# led.net
KiCad netlist of a schematic drawn in EAGLE
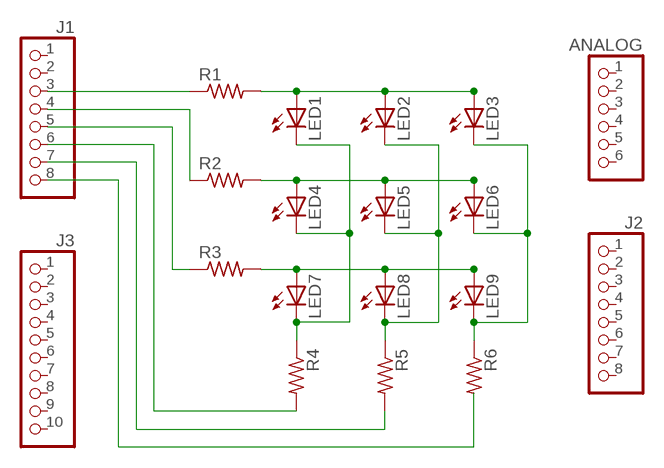
[diagram p0: schematic, sheet 1]

(export (version "E")
  (design (tool "Eeschema 10.0.6"))
  (components
    (comp (ref "ANALOG")
      (value "PINHD-1X6")
      (footprint "eagle-import:1X06")
      (libsource (lib "eagle-import") (part "PINHD-1X6"))
    )
    (comp (ref "J1")
      (value "PINHD-1X8TH")
      (footprint "eagle-import:1X08-TH")
      (libsource (lib "eagle-import") (part "PINHD-1X8TH"))
    )
    (comp (ref "J2")
      (value "PINHD-1X8TH")
      (footprint "eagle-import:1X08-TH")
      (libsource (lib "eagle-import") (part "PINHD-1X8TH"))
    )
    (comp (ref "J3")
      (value "PINHD-1X10TH")
      (footprint "eagle-import:1X10-TH")
      (libsource (lib "eagle-import") (part "PINHD-1X10TH"))
    )
    (comp (ref "LED1")
      (value "LED3MM")
      (footprint "eagle-import:LED3MM")
      (libsource (lib "eagle-import") (part "LED3MM"))
    )
    (comp (ref "LED2")
      (value "LED3MM")
      (footprint "eagle-import:LED3MM")
      (libsource (lib "eagle-import") (part "LED3MM"))
    )
    (comp (ref "LED3")
      (value "LED3MM")
      (footprint "eagle-import:LED3MM")
      (libsource (lib "eagle-import") (part "LED3MM"))
    )
    (comp (ref "LED4")
      (value "LED3MM")
      (footprint "eagle-import:LED3MM")
      (libsource (lib "eagle-import") (part "LED3MM"))
    )
    (comp (ref "LED5")
      (value "LED3MM")
      (footprint "eagle-import:LED3MM")
      (libsource (lib "eagle-import") (part "LED3MM"))
    )
    (comp (ref "LED6")
      (value "LED3MM")
      (footprint "eagle-import:LED3MM")
      (libsource (lib "eagle-import") (part "LED3MM"))
    )
    (comp (ref "LED7")
      (value "LED3MM")
      (footprint "eagle-import:LED3MM")
      (libsource (lib "eagle-import") (part "LED3MM"))
    )
    (comp (ref "LED8")
      (value "LED3MM")
      (footprint "eagle-import:LED3MM")
      (libsource (lib "eagle-import") (part "LED3MM"))
    )
    (comp (ref "LED9")
      (value "LED3MM")
      (footprint "eagle-import:LED3MM")
      (libsource (lib "eagle-import") (part "LED3MM"))
    )
    (comp (ref "R1")
      (value "R-US_0207/10")
      (footprint "eagle-import:0207_10")
      (libsource (lib "eagle-import") (part "R-US_0207/10"))
    )
    (comp (ref "R2")
      (value "R-US_0207/10")
      (footprint "eagle-import:0207_10")
      (libsource (lib "eagle-import") (part "R-US_0207/10"))
    )
    (comp (ref "R3")
      (value "R-US_0207/10")
      (footprint "eagle-import:0207_10")
      (libsource (lib "eagle-import") (part "R-US_0207/10"))
    )
    (comp (ref "R4")
      (value "R-US_0207/10")
      (footprint "eagle-import:0207_10")
      (libsource (lib "eagle-import") (part "R-US_0207/10"))
    )
    (comp (ref "R5")
      (value "R-US_0207/10")
      (footprint "eagle-import:0207_10")
      (libsource (lib "eagle-import") (part "R-US_0207/10"))
    )
    (comp (ref "R6")
      (value "R-US_0207/10")
      (footprint "eagle-import:0207_10")
      (libsource (lib "eagle-import") (part "R-US_0207/10"))
    )
  )
  (nets
    (net (code "1") (name "Net-(J1-Pad3)") (class "Default")
      (node (ref "J1") (pin "3") (pinfunction "3_3") (pintype "passive"))
      (node (ref "R1") (pin "1") (pinfunction "1_1") (pintype "passive"))
    )
    (net (code "2") (name "Net-(J1-Pad4)") (class "Default")
      (node (ref "J1") (pin "4") (pinfunction "4_4") (pintype "passive"))
      (node (ref "R2") (pin "1") (pinfunction "1_1") (pintype "passive"))
    )
    (net (code "3") (name "Net-(J1-Pad5)") (class "Default")
      (node (ref "J1") (pin "5") (pinfunction "5_5") (pintype "passive"))
      (node (ref "R3") (pin "1") (pinfunction "1_1") (pintype "passive"))
    )
    (net (code "4") (name "Net-(J1-Pad6)") (class "Default")
      (node (ref "J1") (pin "6") (pinfunction "6_6") (pintype "passive"))
      (node (ref "R4") (pin "2") (pinfunction "2_2") (pintype "passive"))
    )
    (net (code "5") (name "Net-(J1-Pad7)") (class "Default")
      (node (ref "J1") (pin "7") (pinfunction "7_7") (pintype "passive"))
      (node (ref "R5") (pin "2") (pinfunction "2_2") (pintype "passive"))
    )
    (net (code "6") (name "Net-(J1-Pad8)") (class "Default")
      (node (ref "J1") (pin "8") (pinfunction "8_8") (pintype "passive"))
      (node (ref "R6") (pin "2") (pinfunction "2_2") (pintype "passive"))
    )
    (net (code "7") (name "Net-(LED1-C)") (class "Default")
      (node (ref "LED1") (pin "K") (pinfunction "C_K") (pintype "passive"))
      (node (ref "LED4") (pin "K") (pinfunction "C_K") (pintype "passive"))
      (node (ref "LED7") (pin "K") (pinfunction "C_K") (pintype "passive"))
      (node (ref "R4") (pin "1") (pinfunction "1_1") (pintype "passive"))
    )
    (net (code "8") (name "Net-(LED1-PadA)") (class "Default")
      (node (ref "LED1") (pin "A") (pinfunction "A_A") (pintype "passive"))
      (node (ref "LED2") (pin "A") (pinfunction "A_A") (pintype "passive"))
      (node (ref "LED3") (pin "A") (pinfunction "A_A") (pintype "passive"))
      (node (ref "R1") (pin "2") (pinfunction "2_2") (pintype "passive"))
    )
    (net (code "9") (name "Net-(LED2-C)") (class "Default")
      (node (ref "LED2") (pin "K") (pinfunction "C_K") (pintype "passive"))
      (node (ref "LED5") (pin "K") (pinfunction "C_K") (pintype "passive"))
      (node (ref "LED8") (pin "K") (pinfunction "C_K") (pintype "passive"))
      (node (ref "R5") (pin "1") (pinfunction "1_1") (pintype "passive"))
    )
    (net (code "10") (name "Net-(LED3-C)") (class "Default")
      (node (ref "LED3") (pin "K") (pinfunction "C_K") (pintype "passive"))
      (node (ref "LED6") (pin "K") (pinfunction "C_K") (pintype "passive"))
      (node (ref "LED9") (pin "K") (pinfunction "C_K") (pintype "passive"))
      (node (ref "R6") (pin "1") (pinfunction "1_1") (pintype "passive"))
    )
    (net (code "11") (name "Net-(LED4-PadA)") (class "Default")
      (node (ref "LED4") (pin "A") (pinfunction "A_A") (pintype "passive"))
      (node (ref "LED5") (pin "A") (pinfunction "A_A") (pintype "passive"))
      (node (ref "LED6") (pin "A") (pinfunction "A_A") (pintype "passive"))
      (node (ref "R2") (pin "2") (pinfunction "2_2") (pintype "passive"))
    )
    (net (code "12") (name "Net-(LED7-PadA)") (class "Default")
      (node (ref "LED7") (pin "A") (pinfunction "A_A") (pintype "passive"))
      (node (ref "LED8") (pin "A") (pinfunction "A_A") (pintype "passive"))
      (node (ref "LED9") (pin "A") (pinfunction "A_A") (pintype "passive"))
      (node (ref "R3") (pin "2") (pinfunction "2_2") (pintype "passive"))
    )
    (net (code "13") (name "unconnected-(ANALOG-Pad1)") (class "Default")
      (node (ref "ANALOG") (pin "1") (pinfunction "1_1") (pintype "passive"))
    )
    (net (code "14") (name "unconnected-(ANALOG-Pad2)") (class "Default")
      (node (ref "ANALOG") (pin "2") (pinfunction "2_2") (pintype "passive"))
    )
    (net (code "15") (name "unconnected-(ANALOG-Pad3)") (class "Default")
      (node (ref "ANALOG") (pin "3") (pinfunction "3_3") (pintype "passive"))
    )
    (net (code "16") (name "unconnected-(ANALOG-Pad4)") (class "Default")
      (node (ref "ANALOG") (pin "4") (pinfunction "4_4") (pintype "passive"))
    )
    (net (code "17") (name "unconnected-(ANALOG-Pad5)") (class "Default")
      (node (ref "ANALOG") (pin "5") (pinfunction "5_5") (pintype "passive"))
    )
    (net (code "18") (name "unconnected-(ANALOG-Pad6)") (class "Default")
      (node (ref "ANALOG") (pin "6") (pinfunction "6_6") (pintype "passive"))
    )
    (net (code "19") (name "unconnected-(J1-Pad1)") (class "Default")
      (node (ref "J1") (pin "1") (pinfunction "1_1") (pintype "passive"))
    )
    (net (code "20") (name "unconnected-(J1-Pad2)") (class "Default")
      (node (ref "J1") (pin "2") (pinfunction "2_2") (pintype "passive"))
    )
    (net (code "21") (name "unconnected-(J2-Pad1)") (class "Default")
      (node (ref "J2") (pin "1") (pinfunction "1_1") (pintype "passive"))
    )
    (net (code "22") (name "unconnected-(J2-Pad2)") (class "Default")
      (node (ref "J2") (pin "2") (pinfunction "2_2") (pintype "passive"))
    )
    (net (code "23") (name "unconnected-(J2-Pad3)") (class "Default")
      (node (ref "J2") (pin "3") (pinfunction "3_3") (pintype "passive"))
    )
    (net (code "24") (name "unconnected-(J2-Pad4)") (class "Default")
      (node (ref "J2") (pin "4") (pinfunction "4_4") (pintype "passive"))
    )
    (net (code "25") (name "unconnected-(J2-Pad5)") (class "Default")
      (node (ref "J2") (pin "5") (pinfunction "5_5") (pintype "passive"))
    )
    (net (code "26") (name "unconnected-(J2-Pad6)") (class "Default")
      (node (ref "J2") (pin "6") (pinfunction "6_6") (pintype "passive"))
    )
    (net (code "27") (name "unconnected-(J2-Pad7)") (class "Default")
      (node (ref "J2") (pin "7") (pinfunction "7_7") (pintype "passive"))
    )
    (net (code "28") (name "unconnected-(J2-Pad8)") (class "Default")
      (node (ref "J2") (pin "8") (pinfunction "8_8") (pintype "passive"))
    )
    (net (code "29") (name "unconnected-(J3-Pad1)") (class "Default")
      (node (ref "J3") (pin "1") (pinfunction "1_1") (pintype "passive"))
    )
    (net (code "30") (name "unconnected-(J3-Pad2)") (class "Default")
      (node (ref "J3") (pin "2") (pinfunction "2_2") (pintype "passive"))
    )
    (net (code "31") (name "unconnected-(J3-Pad3)") (class "Default")
      (node (ref "J3") (pin "3") (pinfunction "3_3") (pintype "passive"))
    )
    (net (code "32") (name "unconnected-(J3-Pad4)") (class "Default")
      (node (ref "J3") (pin "4") (pinfunction "4_4") (pintype "passive"))
    )
    (net (code "33") (name "unconnected-(J3-Pad5)") (class "Default")
      (node (ref "J3") (pin "5") (pinfunction "5_5") (pintype "passive"))
    )
    (net (code "34") (name "unconnected-(J3-Pad6)") (class "Default")
      (node (ref "J3") (pin "6") (pinfunction "6_6") (pintype "passive"))
    )
    (net (code "35") (name "unconnected-(J3-Pad7)") (class "Default")
      (node (ref "J3") (pin "7") (pinfunction "7_7") (pintype "passive"))
    )
    (net (code "36") (name "unconnected-(J3-Pad8)") (class "Default")
      (node (ref "J3") (pin "8") (pinfunction "8_8") (pintype "passive"))
    )
    (net (code "37") (name "unconnected-(J3-Pad9)") (class "Default")
      (node (ref "J3") (pin "9") (pinfunction "9_9") (pintype "passive"))
    )
    (net (code "38") (name "unconnected-(J3-Pad10)") (class "Default")
      (node (ref "J3") (pin "10") (pinfunction "10_10") (pintype "passive"))
    )
  )
)
